# xmega32A4U.net
KiCad netlist of a schematic drawn in Altium Designer
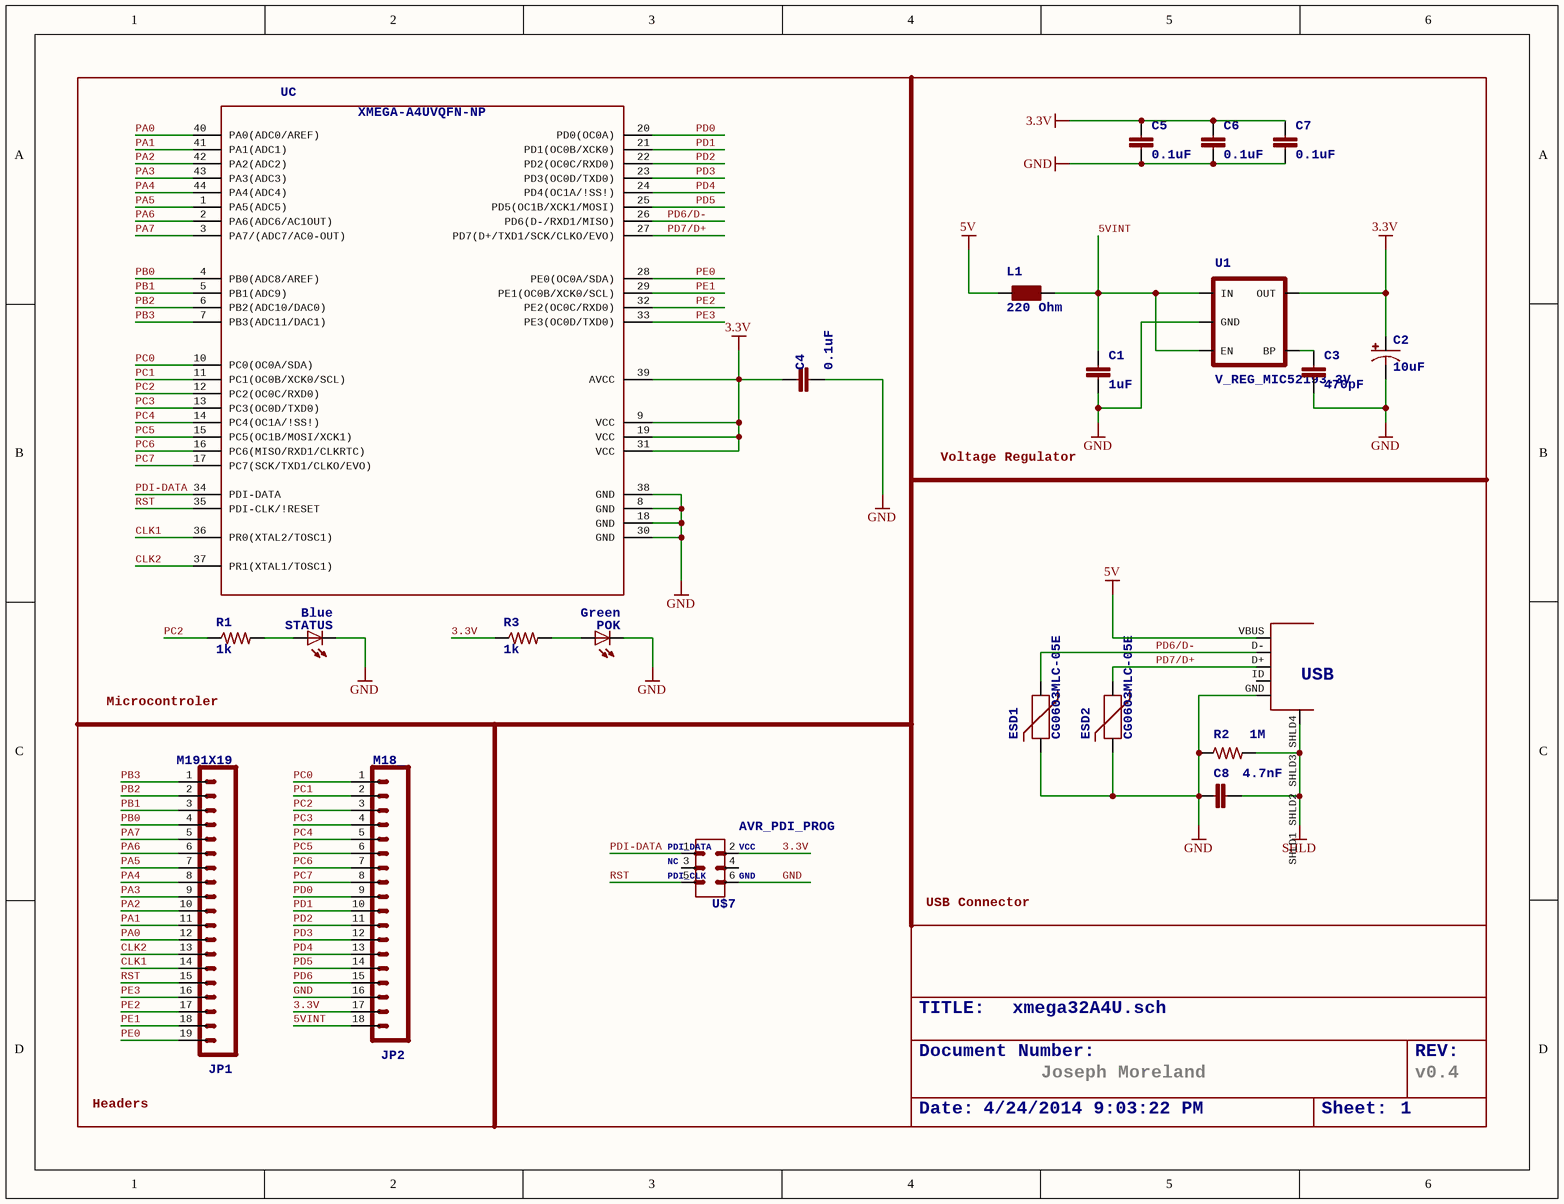
[diagram p0: xmega32A4U.SchDoc]

(export (version "E")
  (design (tool "Eeschema 10.0.6"))
  (components
    (comp (ref "C1")
      (value "1uF")
      (footprint "0603-CAP")
      (description "<b>Capacitor</b>\nStandard 0603 ceramic capacitor, and 0.1\" leaded capacitor.")
      (fields (field (name "PARTNO") "C0603C105K3PACTU"))
      (libsource (lib "JCM-Capacitors") (part "CAP0603-CAP"))
    )
    (comp (ref "C2")
      (value "10uF")
      (footprint "EIA3216")
      (fields (field (name "PARTNO") "T494A106M020AT"))
      (libsource (lib "SparkFun-Capacitors") (part "CAP_POL1206"))
    )
    (comp (ref "C3")
      (value "470pF")
      (footprint "0603-CAP")
      (description "<b>Capacitor</b>\nStandard 0603 ceramic capacitor, and 0.1\" leaded capacitor.")
      (fields (field (name "PARTNO") "C0603C471K5RACTU"))
      (libsource (lib "JCM-Capacitors") (part "CAP0603-CAP"))
    )
    (comp (ref "C4")
      (value "0.1uF")
      (footprint "0402-CAP")
      (description "<b>Capacitor</b>\nStandard 0603 ceramic capacitor, and 0.1\" leaded capacitor.")
      (libsource (lib "JCM-Capacitors") (part "CAP0402-CAP"))
    )
    (comp (ref "C5")
      (value "0.1uF")
      (footprint "0402-CAP")
      (description "<b>Capacitor</b>\nStandard 0603 ceramic capacitor, and 0.1\" leaded capacitor.")
      (fields (field (name "PARTNO") "GMK105BJ104KV-F"))
      (libsource (lib "") (part "CAP0402-CAP_1"))
    )
    (comp (ref "C6")
      (value "0.1uF")
      (footprint "0402-CAP")
      (description "<b>Capacitor</b>\nStandard 0603 ceramic capacitor, and 0.1\" leaded capacitor.")
      (fields (field (name "PARTNO") "GMK105BJ104KV-F"))
      (libsource (lib "") (part "CAP0402-CAP_1"))
    )
    (comp (ref "C7")
      (value "0.1uF")
      (footprint "0402-CAP")
      (description "<b>Capacitor</b>\nStandard 0603 ceramic capacitor, and 0.1\" leaded capacitor.")
      (fields (field (name "PARTNO") "GMK105BJ104KV-F"))
      (libsource (lib "") (part "CAP0402-CAP_1"))
    )
    (comp (ref "C8")
      (value "4.7nF")
      (footprint "0402-CAP")
      (description "<b>Capacitor</b>\nStandard 0603 ceramic capacitor, and 0.1\" leaded capacitor.")
      (libsource (lib "JCM-Capacitors") (part "CAP0402-CAP"))
    )
    (comp (ref "ESD1")
      (value "CG0603MLC-05E")
      (footprint "0603-CHIPGUARD")
      (description "ESD suppresor \nChipGuard MLC")
      (libsource (lib "JCM") (part "CG0603MLC"))
    )
    (comp (ref "ESD2")
      (value "CG0603MLC-05E")
      (footprint "0603-CHIPGUARD")
      (description "ESD suppresor \nChipGuard MLC")
      (libsource (lib "JCM") (part "CG0603MLC"))
    )
    (comp (ref "JP1")
      (value "M191X19")
      (footprint "1X19")
      (description "1x19 .1\" header")
      (fields (field (name "PARTNO") "M20-9732046"))
      (libsource (lib "SparkFun-Connectors") (part "M191X19"))
    )
    (comp (ref "JP2")
      (value "M18_")
      (footprint "1X18")
      (description "1x18 .1\" header")
      (fields (field (name "PARTNO") "68000-418HLF"))
      (libsource (lib "SparkFun-Connectors") (part "M18_"))
    )
    (comp (ref "L1")
      (value "220 Ohm")
      (footprint "0603")
      (fields (field (name "PARTNO") "MPZ1608S221A"))
      (libsource (lib "wuerth-elektronik") (part "WE-CBF_0603"))
    )
    (comp (ref "POK")
      (value "Green")
      (footprint "LED-0603")
      (fields (field (name "PARTNO") "LTST-C190KGKT"))
      (libsource (lib "SparkFun-LED") (part "LED0603"))
    )
    (comp (ref "R1")
      (value "1k")
      (footprint "0603-RES")
      (description "<b>Resistor</b>\nBasic schematic elements and footprints for 0603, 1206, and PTH resistors.")
      (fields (field (name "PARTNO") "RC0603FR-071KL"))
      (libsource (lib "JCM-Resistors") (part "RESISTOR0603-RES"))
    )
    (comp (ref "R2")
      (value "1M")
      (footprint "0402-RES")
      (description "<b>Resistor</b>\nBasic schematic elements and footprints for 0603, 1206, and PTH resistors.")
      (libsource (lib "JCM-Resistors") (part "RESISTOR0402-RES"))
    )
    (comp (ref "R3")
      (value "1k")
      (footprint "0603-RES")
      (description "<b>Resistor</b>\nBasic schematic elements and footprints for 0603, 1206, and PTH resistors.")
      (fields (field (name "PARTNO") "RC0603FR-071KL"))
      (libsource (lib "JCM-Resistors") (part "RESISTOR0603-RES"))
    )
    (comp (ref "STATUS")
      (value "Blue")
      (footprint "LED-0603")
      (fields (field (name "PARTNO") "LTST-C191TBKT"))
      (libsource (lib "SparkFun-LED") (part "LED0603"))
    )
    (comp (ref "U$4")
      (value "USB-MINIB")
      (footprint "USB-MINI-B-UX60-MB-5S8")
      (fields (field (name "PARTNO") "UX60-MB-5S8") (field (name "USB") "USB"))
      (libsource (lib "JCM-Connectors") (part "USB-MINIB"))
    )
    (comp (ref "U$7")
      (value "AVR_PDI_PROG")
      (footprint "AVR_50MIL_PROG")
      (fields
        (field (name "PARTNO") "LPPB032NFSP-RC")
        (field (name "NC") "NC")
        (field (name "GND") "GND")
        (field (name "VCC") "VCC")
        (field (name "PDI_DATA") "PDI_DATA")
        (field (name "PDI_CLK") "PDI_CLK")
      )
      (libsource (lib "JCM-Connectors") (part "AVR_PDI_PROG"))
    )
    (comp (ref "U1")
      (value "V_REG_MIC52193.3V")
      (footprint "SOT23-5")
      (fields (field (name "PARTNO") "MIC5219-3.3YM5 TR"))
      (libsource (lib "SparkFun-PowerIC") (part "V_REG_MIC52193.3V"))
    )
    (comp (ref "UC")
      (value "XMEGA-A4UVQFN-NP")
      (footprint "QFN44-NOPAD")
      (description "Atmel XMega A4 series processor")
      (fields (field (name "PARTNO") "ATXMEGA32A4U-MH"))
      (libsource (lib "JCM-IC") (part "XMEGA-A4UVQFN-NP"))
    )
  )
  (nets
    (net (code "1") (name "/5VINT") (class "Default")
      (node (ref "C1") (pin "1") (pinfunction "1_1") (pintype "passive"))
      (node (ref "JP2") (pin "18") (pinfunction "18_18") (pintype "passive"))
      (node (ref "L1") (pin "2") (pinfunction "2_2") (pintype "passive"))
      (node (ref "U1") (pin "1") (pinfunction "IN_1") (pintype "passive"))
      (node (ref "U1") (pin "3") (pinfunction "EN_3") (pintype "passive"))
    )
    (net (code "2") (name "/CLK1") (class "Default")
      (node (ref "JP1") (pin "14") (pinfunction "14_14") (pintype "passive"))
      (node (ref "UC") (pin "36") (pinfunction "PR0(XTAL2/TOSC1)_36") (pintype "passive"))
    )
    (net (code "3") (name "/CLK2") (class "Default")
      (node (ref "JP1") (pin "13") (pinfunction "13_13") (pintype "passive"))
      (node (ref "UC") (pin "37") (pinfunction "PR1(XTAL1/TOSC1)_37") (pintype "passive"))
    )
    (net (code "4") (name "/PA0") (class "Default")
      (node (ref "JP1") (pin "12") (pinfunction "12_12") (pintype "passive"))
      (node (ref "UC") (pin "40") (pinfunction "PA0(ADC0/AREF)_40") (pintype "passive"))
    )
    (net (code "5") (name "/PA1") (class "Default")
      (node (ref "JP1") (pin "11") (pinfunction "11_11") (pintype "passive"))
      (node (ref "UC") (pin "41") (pinfunction "PA1(ADC1)_41") (pintype "passive"))
    )
    (net (code "6") (name "/PA2") (class "Default")
      (node (ref "JP1") (pin "10") (pinfunction "10_10") (pintype "passive"))
      (node (ref "UC") (pin "42") (pinfunction "PA2(ADC2)_42") (pintype "passive"))
    )
    (net (code "7") (name "/PA3") (class "Default")
      (node (ref "JP1") (pin "9") (pinfunction "9_9") (pintype "passive"))
      (node (ref "UC") (pin "43") (pinfunction "PA3(ADC3)_43") (pintype "passive"))
    )
    (net (code "8") (name "/PA4") (class "Default")
      (node (ref "JP1") (pin "8") (pinfunction "8_8") (pintype "passive"))
      (node (ref "UC") (pin "44") (pinfunction "PA4(ADC4)_44") (pintype "passive"))
    )
    (net (code "9") (name "/PA5") (class "Default")
      (node (ref "JP1") (pin "7") (pinfunction "7_7") (pintype "passive"))
      (node (ref "UC") (pin "1") (pinfunction "PA5(ADC5)_1") (pintype "passive"))
    )
    (net (code "10") (name "/PA6") (class "Default")
      (node (ref "JP1") (pin "6") (pinfunction "6_6") (pintype "passive"))
      (node (ref "UC") (pin "2") (pinfunction "PA6(ADC6/AC1OUT)_2") (pintype "passive"))
    )
    (net (code "11") (name "/PA7") (class "Default")
      (node (ref "JP1") (pin "5") (pinfunction "5_5") (pintype "passive"))
      (node (ref "UC") (pin "3") (pinfunction "PA7/(ADC7/AC0-OUT)_3") (pintype "passive"))
    )
    (net (code "12") (name "/PB0") (class "Default")
      (node (ref "JP1") (pin "4") (pinfunction "4_4") (pintype "passive"))
      (node (ref "UC") (pin "4") (pinfunction "PB0(ADC8/AREF)_4") (pintype "passive"))
    )
    (net (code "13") (name "/PB1") (class "Default")
      (node (ref "JP1") (pin "3") (pinfunction "3_3") (pintype "passive"))
      (node (ref "UC") (pin "5") (pinfunction "PB1(ADC9)_5") (pintype "passive"))
    )
    (net (code "14") (name "/PB2") (class "Default")
      (node (ref "JP1") (pin "2") (pinfunction "2_2") (pintype "passive"))
      (node (ref "UC") (pin "6") (pinfunction "PB2(ADC10/DAC0)_6") (pintype "passive"))
    )
    (net (code "15") (name "/PB3") (class "Default")
      (node (ref "JP1") (pin "1") (pinfunction "1_1") (pintype "passive"))
      (node (ref "UC") (pin "7") (pinfunction "PB3(ADC11/DAC1)_7") (pintype "passive"))
    )
    (net (code "16") (name "/PC0") (class "Default")
      (node (ref "JP2") (pin "1") (pinfunction "1_1") (pintype "passive"))
      (node (ref "UC") (pin "10") (pinfunction "PC0(OC0A/SDA)_10") (pintype "passive"))
    )
    (net (code "17") (name "/PC1") (class "Default")
      (node (ref "JP2") (pin "2") (pinfunction "2_2") (pintype "passive"))
      (node (ref "UC") (pin "11") (pinfunction "PC1(OC0B/XCK0/SCL)_11") (pintype "passive"))
    )
    (net (code "18") (name "/PC2") (class "Default")
      (node (ref "JP2") (pin "3") (pinfunction "3_3") (pintype "passive"))
      (node (ref "R1") (pin "1") (pinfunction "1_1") (pintype "passive"))
      (node (ref "UC") (pin "12") (pinfunction "PC2(OC0C/RXD0)_12") (pintype "passive"))
    )
    (net (code "19") (name "/PC3") (class "Default")
      (node (ref "JP2") (pin "4") (pinfunction "4_4") (pintype "passive"))
      (node (ref "UC") (pin "13") (pinfunction "PC3(OC0D/TXD0)_13") (pintype "passive"))
    )
    (net (code "20") (name "/PC4") (class "Default")
      (node (ref "JP2") (pin "5") (pinfunction "5_5") (pintype "passive"))
      (node (ref "UC") (pin "14") (pinfunction "PC4(OC1A/!SS!)_14") (pintype "passive"))
    )
    (net (code "21") (name "/PC5") (class "Default")
      (node (ref "JP2") (pin "6") (pinfunction "6_6") (pintype "passive"))
      (node (ref "UC") (pin "15") (pinfunction "PC5(OC1B/MOSI/XCK1)_15") (pintype "passive"))
    )
    (net (code "22") (name "/PC6") (class "Default")
      (node (ref "JP2") (pin "7") (pinfunction "7_7") (pintype "passive"))
      (node (ref "UC") (pin "16") (pinfunction "PC6(MISO/RXD1/CLKRTC)_16") (pintype "passive"))
    )
    (net (code "23") (name "/PC7") (class "Default")
      (node (ref "JP2") (pin "8") (pinfunction "8_8") (pintype "passive"))
      (node (ref "UC") (pin "17") (pinfunction "PC7(SCK/TXD1/CLKO/EVO)_17") (pintype "passive"))
    )
    (net (code "24") (name "/PD0") (class "Default")
      (node (ref "JP2") (pin "9") (pinfunction "9_9") (pintype "passive"))
      (node (ref "UC") (pin "20") (pinfunction "PD0(OC0A)_20") (pintype "passive"))
    )
    (net (code "25") (name "/PD1") (class "Default")
      (node (ref "JP2") (pin "10") (pinfunction "10_10") (pintype "passive"))
      (node (ref "UC") (pin "21") (pinfunction "PD1(OC0B/XCK0)_21") (pintype "passive"))
    )
    (net (code "26") (name "/PD2") (class "Default")
      (node (ref "JP2") (pin "11") (pinfunction "11_11") (pintype "passive"))
      (node (ref "UC") (pin "22") (pinfunction "PD2(OC0C/RXD0)_22") (pintype "passive"))
    )
    (net (code "27") (name "/PD3") (class "Default")
      (node (ref "JP2") (pin "12") (pinfunction "12_12") (pintype "passive"))
      (node (ref "UC") (pin "23") (pinfunction "PD3(OC0D/TXD0)_23") (pintype "passive"))
    )
    (net (code "28") (name "/PD4") (class "Default")
      (node (ref "JP2") (pin "13") (pinfunction "13_13") (pintype "passive"))
      (node (ref "UC") (pin "24") (pinfunction "PD4(OC1A/!SS!)_24") (pintype "passive"))
    )
    (net (code "29") (name "/PD5") (class "Default")
      (node (ref "JP2") (pin "14") (pinfunction "14_14") (pintype "passive"))
      (node (ref "UC") (pin "25") (pinfunction "PD5(OC1B/XCK1/MOSI)_25") (pintype "passive"))
    )
    (net (code "30") (name "/PD6") (class "Default")
      (node (ref "JP2") (pin "15") (pinfunction "15_15") (pintype "passive"))
    )
    (net (code "31") (name "/PD6{slash}D-") (class "Default")
      (node (ref "ESD1") (pin "P$2") (pinfunction "P$2_P$2") (pintype "passive"))
      (node (ref "U$4") (pin "D-") (pinfunction "D-_D-") (pintype "passive"))
      (node (ref "UC") (pin "26") (pinfunction "PD6(D-/RXD1/MISO)_26") (pintype "passive"))
    )
    (net (code "32") (name "/PD7{slash}D+") (class "Default")
      (node (ref "ESD2") (pin "P$2") (pinfunction "P$2_P$2") (pintype "passive"))
      (node (ref "U$4") (pin "D+") (pinfunction "D+_D+") (pintype "passive"))
      (node (ref "UC") (pin "27") (pinfunction "PD7(D+/TXD1/SCK/CLKO/EVO)_27") (pintype "passive"))
    )
    (net (code "33") (name "/PDI-DATA") (class "Default")
      (node (ref "U$7") (pin "1") (pinfunction "PDI_DATA_1") (pintype "passive"))
      (node (ref "UC") (pin "34") (pinfunction "PDI-DATA_34") (pintype "passive"))
    )
    (net (code "34") (name "/PE0") (class "Default")
      (node (ref "JP1") (pin "19") (pinfunction "19_19") (pintype "passive"))
      (node (ref "UC") (pin "28") (pinfunction "PE0(OC0A/SDA)_28") (pintype "passive"))
    )
    (net (code "35") (name "/PE1") (class "Default")
      (node (ref "JP1") (pin "18") (pinfunction "18_18") (pintype "passive"))
      (node (ref "UC") (pin "29") (pinfunction "PE1(OC0B/XCK0/SCL)_29") (pintype "passive"))
    )
    (net (code "36") (name "/PE2") (class "Default")
      (node (ref "JP1") (pin "17") (pinfunction "17_17") (pintype "passive"))
      (node (ref "UC") (pin "32") (pinfunction "PE2(OC0C/RXD0)_32") (pintype "passive"))
    )
    (net (code "37") (name "/PE3") (class "Default")
      (node (ref "JP1") (pin "16") (pinfunction "16_16") (pintype "passive"))
      (node (ref "UC") (pin "33") (pinfunction "PE3(OC0D/TXD0)_33") (pintype "passive"))
    )
    (net (code "38") (name "/RST") (class "Default")
      (node (ref "JP1") (pin "15") (pinfunction "15_15") (pintype "passive"))
      (node (ref "U$7") (pin "5") (pinfunction "PDI_CLK_5") (pintype "passive"))
      (node (ref "UC") (pin "35") (pinfunction "PDI-CLK/!RESET_35") (pintype "passive"))
    )
    (net (code "39") (name "3.3V") (class "Default")
      (node (ref "C2") (pin "A") (pinfunction "+_A") (pintype "passive"))
      (node (ref "C4") (pin "1") (pinfunction "1_1") (pintype "passive"))
      (node (ref "C5") (pin "1") (pinfunction "1_1") (pintype "passive"))
      (node (ref "C6") (pin "1") (pinfunction "1_1") (pintype "passive"))
      (node (ref "C7") (pin "1") (pinfunction "1_1") (pintype "passive"))
      (node (ref "JP2") (pin "17") (pinfunction "17_17") (pintype "passive"))
      (node (ref "R3") (pin "1") (pinfunction "1_1") (pintype "passive"))
      (node (ref "U$7") (pin "2") (pinfunction "VCC_2") (pintype "passive"))
      (node (ref "U1") (pin "5") (pinfunction "OUT_5") (pintype "passive"))
      (node (ref "UC") (pin "19") (pinfunction "VCC_19") (pintype "power_in"))
      (node (ref "UC") (pin "31") (pinfunction "VCC_31") (pintype "power_in"))
      (node (ref "UC") (pin "39") (pinfunction "AVCC_39") (pintype "power_in"))
      (node (ref "UC") (pin "9") (pinfunction "VCC_9") (pintype "power_in"))
    )
    (net (code "40") (name "5V") (class "Default")
      (node (ref "L1") (pin "1") (pinfunction "1_1") (pintype "passive"))
      (node (ref "U$4") (pin "VBUS") (pinfunction "VBUS_VBUS") (pintype "passive"))
    )
    (net (code "41") (name "GND") (class "Default")
      (node (ref "C1") (pin "2") (pinfunction "2_2") (pintype "passive"))
      (node (ref "C2") (pin "C") (pinfunction "-_C") (pintype "passive"))
      (node (ref "C3") (pin "2") (pinfunction "2_2") (pintype "passive"))
      (node (ref "C4") (pin "2") (pinfunction "2_2") (pintype "passive"))
      (node (ref "C5") (pin "2") (pinfunction "2_2") (pintype "passive"))
      (node (ref "C6") (pin "2") (pinfunction "2_2") (pintype "passive"))
      (node (ref "C7") (pin "2") (pinfunction "2_2") (pintype "passive"))
      (node (ref "C8") (pin "1") (pinfunction "1_1") (pintype "passive"))
      (node (ref "ESD1") (pin "P$1") (pinfunction "P$1_P$1") (pintype "passive"))
      (node (ref "ESD2") (pin "P$1") (pinfunction "P$1_P$1") (pintype "passive"))
      (node (ref "JP2") (pin "16") (pinfunction "16_16") (pintype "passive"))
      (node (ref "POK") (pin "C") (pinfunction "C_C") (pintype "passive"))
      (node (ref "R2") (pin "1") (pinfunction "1_1") (pintype "passive"))
      (node (ref "STATUS") (pin "C") (pinfunction "C_C") (pintype "passive"))
      (node (ref "U$4") (pin "GND") (pinfunction "GND_GND") (pintype "passive"))
      (node (ref "U$7") (pin "6") (pinfunction "GND_6") (pintype "passive"))
      (node (ref "U1") (pin "2") (pinfunction "GND_2") (pintype "passive"))
      (node (ref "UC") (pin "18") (pinfunction "GND_18") (pintype "power_in"))
      (node (ref "UC") (pin "30") (pinfunction "GND_30") (pintype "power_in"))
      (node (ref "UC") (pin "38") (pinfunction "GND_38") (pintype "power_in"))
      (node (ref "UC") (pin "8") (pinfunction "GND_8") (pintype "power_in"))
    )
    (net (code "42") (name "Net-(POK-PadA)") (class "Default")
      (node (ref "POK") (pin "A") (pinfunction "A_A") (pintype "passive"))
      (node (ref "R3") (pin "2") (pinfunction "2_2") (pintype "passive"))
    )
    (net (code "43") (name "Net-(R1-Pad2)") (class "Default")
      (node (ref "R1") (pin "2") (pinfunction "2_2") (pintype "passive"))
      (node (ref "STATUS") (pin "A") (pinfunction "A_A") (pintype "passive"))
    )
    (net (code "44") (name "Net-(U1-BP)") (class "Default")
      (node (ref "C3") (pin "1") (pinfunction "1_1") (pintype "passive"))
      (node (ref "U1") (pin "4") (pinfunction "BP_4") (pintype "passive"))
    )
    (net (code "45") (name "SHLD") (class "Default")
      (node (ref "C8") (pin "2") (pinfunction "2_2") (pintype "passive"))
      (node (ref "R2") (pin "2") (pinfunction "2_2") (pintype "passive"))
      (node (ref "U$4") (pin "SHLD1_SHLD2_SHLD3_SHLD4") (pinfunction "SHLD_SHLD1_SHLD2_SHLD3_SHLD4") (pintype "passive"))
    )
    (net (code "46") (name "unconnected-(U$4-PadID)") (class "Default")
      (node (ref "U$4") (pin "ID") (pinfunction "ID_ID") (pintype "passive"))
    )
    (net (code "47") (name "unconnected-(U$7-NC-Pad3)") (class "Default")
      (node (ref "U$7") (pin "3") (pinfunction "NC_3") (pintype "passive"))
    )
    (net (code "48") (name "unconnected-(U$7-NC1-Pad4)") (class "Default")
      (node (ref "U$7") (pin "4") (pinfunction "NC1_4") (pintype "passive"))
    )
  )
)
